# Magneto.net
KiCad netlist of a schematic drawn in Altium Designer
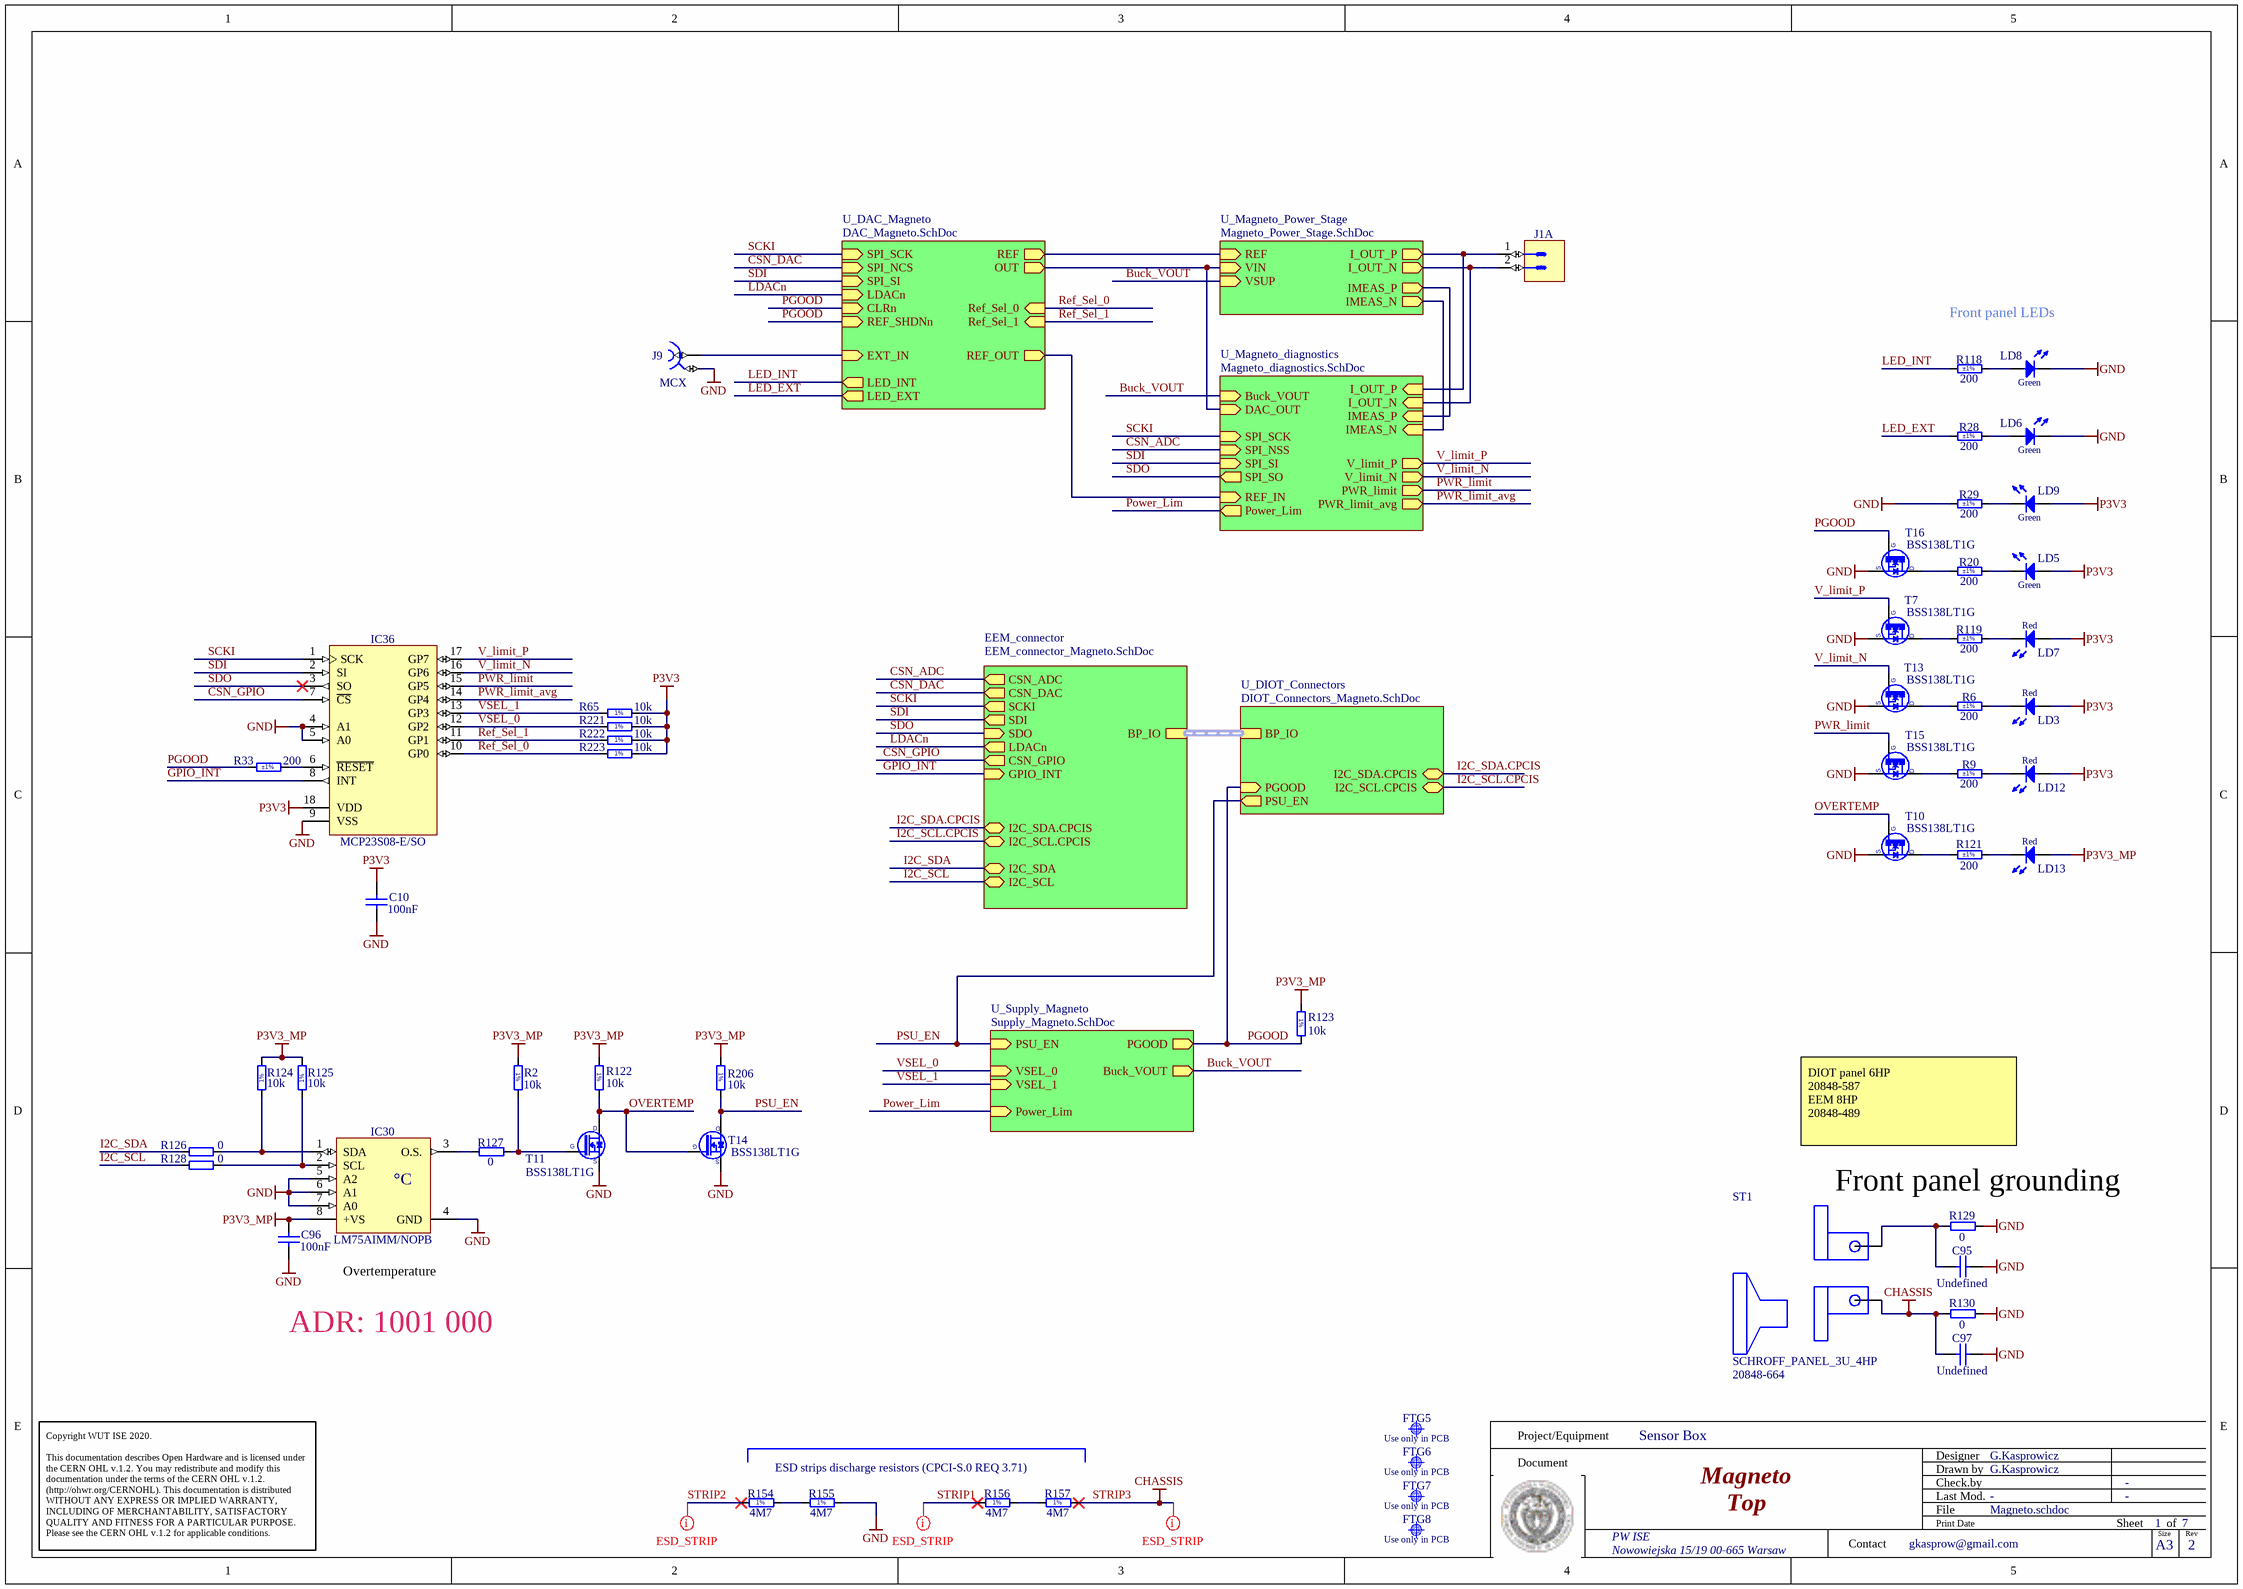
[diagram p0: Magneto.schdoc]

(export (version "E")
  (design (tool "Eeschema 10.0.6"))
  (components
    (comp (ref "C10")
      (value "100nF")
      (footprint "CAPC1005X55N")
      (description "Non-polarised capacitor")
      (fields
        (field (name "PART NUMBER") "CC0402_100NF_16V_10%_X5R")
        (field (name "VOLTAGE") "16V")
        (field (name "AUTHOR") "CERN DEM JLC")
      )
      (libsource (lib "Capacitors") (part "Capacitor - non polarized"))
    )
    (comp (ref "C95")
      (value "Undefined")
      (footprint "CAPC2012X135N")
      (description "Non-polarised capacitor")
      (fields (field (name "PART NUMBER") "CC0805_NO-VALUE") (field (name "AUTHOR") "CERN DEM JLC"))
      (libsource (lib "Capacitors") (part "Capacitor - non polarized"))
    )
    (comp (ref "C96")
      (value "100nF")
      (footprint "CAPC1005X55N")
      (description "Non-polarised capacitor")
      (fields
        (field (name "PART NUMBER") "CC0402_100NF_16V_10%_X5R")
        (field (name "VOLTAGE") "16V")
        (field (name "AUTHOR") "CERN DEM JLC")
      )
      (libsource (lib "Capacitors") (part "Capacitor - non polarized"))
    )
    (comp (ref "C97")
      (value "Undefined")
      (footprint "CAPC2012X135N")
      (description "Non-polarised capacitor")
      (fields (field (name "PART NUMBER") "CC0805_NO-VALUE") (field (name "AUTHOR") "CERN DEM JLC"))
      (libsource (lib "Capacitors") (part "Capacitor - non polarized"))
    )
    (comp (ref "FTG5")
      (value "Use only in PCB")
      (footprint "FIDUCIAL_TOP_C100-200")
      (description "Fiducial Target")
      (fields (field (name "PART NUMBER") "FIDUCIAL_TARGET_C100-200") (field (name "AUTHOR") "CERN DEM JLC"))
      (libsource (lib "Eletro-mechanical") (part "Fiducial Target"))
    )
    (comp (ref "FTG6")
      (value "Use only in PCB")
      (footprint "FIDUCIAL_TOP_S100-200")
      (description "Fiducial Target")
      (fields (field (name "PART NUMBER") "FIDUCIAL_TARGET_S100-200") (field (name "AUTHOR") "CERN DEM JLC"))
      (libsource (lib "Eletro-mechanical") (part "Fiducial Target"))
    )
    (comp (ref "FTG7")
      (value "Use only in PCB")
      (footprint "FIDUCIAL_TOP_S100-200")
      (description "Fiducial Target")
      (fields (field (name "PART NUMBER") "FIDUCIAL_TARGET_S100-200") (field (name "AUTHOR") "CERN DEM JLC"))
      (libsource (lib "Eletro-mechanical") (part "Fiducial Target"))
    )
    (comp (ref "FTG8")
      (value "Use only in PCB")
      (footprint "FIDUCIAL_TOP_S100-200")
      (description "Fiducial Target")
      (fields (field (name "PART NUMBER") "FIDUCIAL_TARGET_S100-200") (field (name "AUTHOR") "CERN DEM JLC"))
      (libsource (lib "Eletro-mechanical") (part "Fiducial Target"))
    )
    (comp (ref "IC30")
      (value "LM75AIMM/NOPB")
      (footprint "SOP65P490X109-8N")
      (description "Digital Temperature Sensor and Thermal Watchdog with Two-Wire Interface")
      (fields (field (name "AUTHOR") "CERN DEM JLC"))
      (libsource (lib "ICs And Semiconductors") (part "LM75"))
    )
    (comp (ref "IC36")
      (value "MCP23S08-E/SO")
      (footprint "SOIC127P1030X265-18N")
      (description "8-Bit I/O Expander with Serial Interface SPI")
      (fields (field (name "AUTHOR") "CERN DEM HF"))
      (libsource (lib "ICs And Semiconductors") (part "MCP23S08-E/SO"))
    )
    (comp (ref "J1")
      (value "~")
      (footprint "PHOENIX_1817615")
      (description "Connector 2 Male+2MTG")
      (fields
        (field (name "PART NUMBER") "1817615 (MC 1,5/ 2-GF-3,5-LR)")
        (field (name "MANUFACTURER1 PART NUMBER") "1817615")
        (field (name "AUTHOR") "CERN DEM BC")
      )
      (libsource (lib "Connectors") (part "Connector 2 Male+2MTG"))
    )
    (comp (ref "J9")
      (value "MCX")
      (footprint "AMPHENOL_919-383J-51A")
      (fields
        (field (name "PART NUMBER") "AMPHENOL_919-383J-51A")
        (field (name "MANUFACTURER1 PART NUMBER") "919-383J-51A")
        (field (name "AUTHOR") "CERN DEM BC")
      )
      (libsource (lib "Connectors") (part "Coax_1Female_1Shield"))
    )
    (comp (ref "LD3")
      (value "Red")
      (footprint "LED_DIALIGHT_555-200")
      (description "LED Red 1C 2A")
      (fields
        (field (name "PART NUMBER") "LED_DIALIGHT_555-2001F")
        (field (name "MANUFACTURER1 PART NUMBER") "555-2001F")
        (field (name "AUTHOR") "CERN DEM JMW")
      )
      (libsource (lib "ICs And Semiconductors") (part "LED Red 1C 2A"))
    )
    (comp (ref "LD5")
      (value "Green")
      (footprint "LED_DIALIGHT_555-230")
      (description "LED Green 1C 2A")
      (fields
        (field (name "PART NUMBER") "LED_DIALIGHT_555-2301F")
        (field (name "MANUFACTURER1 PART NUMBER") "555-2301F")
        (field (name "AUTHOR") "CERN DEM JMW")
      )
      (libsource (lib "ICs And Semiconductors") (part "LED Green 1C 2A"))
    )
    (comp (ref "LD6")
      (value "Green")
      (footprint "LED_DIALIGHT_555-230")
      (description "LED Green 1C 2A")
      (fields
        (field (name "PART NUMBER") "LED_DIALIGHT_555-2301F")
        (field (name "MANUFACTURER1 PART NUMBER") "555-2301F")
        (field (name "AUTHOR") "CERN DEM JMW")
      )
      (libsource (lib "ICs And Semiconductors") (part "LED Green 1C 2A"))
    )
    (comp (ref "LD7")
      (value "Red")
      (footprint "LED_DIALIGHT_555-200")
      (description "LED Red 1C 2A")
      (fields
        (field (name "PART NUMBER") "LED_DIALIGHT_555-2001F")
        (field (name "MANUFACTURER1 PART NUMBER") "555-2001F")
        (field (name "AUTHOR") "CERN DEM JMW")
      )
      (libsource (lib "ICs And Semiconductors") (part "LED Red 1C 2A"))
    )
    (comp (ref "LD8")
      (value "Green")
      (footprint "LED_DIALIGHT_555-230")
      (description "LED Green 1C 2A")
      (fields
        (field (name "PART NUMBER") "LED_DIALIGHT_555-2301F")
        (field (name "MANUFACTURER1 PART NUMBER") "555-2301F")
        (field (name "AUTHOR") "CERN DEM JMW")
      )
      (libsource (lib "ICs And Semiconductors") (part "LED Green 1C 2A"))
    )
    (comp (ref "LD9")
      (value "Green")
      (footprint "LED_DIALIGHT_555-230")
      (description "LED Green 1C 2A")
      (fields
        (field (name "PART NUMBER") "LED_DIALIGHT_555-2301F")
        (field (name "MANUFACTURER1 PART NUMBER") "555-2301F")
        (field (name "AUTHOR") "CERN DEM JMW")
      )
      (libsource (lib "ICs And Semiconductors") (part "LED Green 1C 2A"))
    )
    (comp (ref "LD12")
      (value "Red")
      (footprint "LED_DIALIGHT_555-200")
      (description "LED Red 1C 2A")
      (fields
        (field (name "PART NUMBER") "LED_DIALIGHT_555-2001F")
        (field (name "MANUFACTURER1 PART NUMBER") "555-2001F")
        (field (name "AUTHOR") "CERN DEM JMW")
      )
      (libsource (lib "ICs And Semiconductors") (part "LED Red 1C 2A"))
    )
    (comp (ref "LD13")
      (value "Red")
      (footprint "LED_DIALIGHT_555-200")
      (description "LED Red 1C 2A")
      (fields
        (field (name "PART NUMBER") "LED_DIALIGHT_555-2001F")
        (field (name "MANUFACTURER1 PART NUMBER") "555-2001F")
        (field (name "AUTHOR") "CERN DEM JMW")
      )
      (libsource (lib "ICs And Semiconductors") (part "LED Red 1C 2A"))
    )
    (comp (ref "R2")
      (value "10k")
      (footprint "RESC1005X40N")
      (description "Resistor - 1%")
      (fields
        (field (name "PART NUMBER") "R0402_10K_1%_0.0625W_100PPM")
        (field (name "POWER") "0.0625W")
        (field (name "AUTHOR") "CERN DEM JLC")
      )
      (libsource (lib "Resistors") (part "Resistor - 1%"))
    )
    (comp (ref "R6")
      (value "200")
      (footprint "RESC1608X55N")
      (description "Resistor - 1%")
      (fields
        (field (name "TOLERANCE") "±1%")
        (field (name "PART NUMBER") "R0603_200R_1%_0.1W_100PPM")
        (field (name "POWER") "0.1W")
        (field (name "AUTHOR") "CERN DEM JLC")
      )
      (libsource (lib "") (part "Resistor - 1%_1"))
    )
    (comp (ref "R9")
      (value "200")
      (footprint "RESC1608X55N")
      (description "Resistor - 1%")
      (fields
        (field (name "TOLERANCE") "±1%")
        (field (name "PART NUMBER") "R0603_200R_1%_0.1W_100PPM")
        (field (name "POWER") "0.1W")
        (field (name "AUTHOR") "CERN DEM JLC")
      )
      (libsource (lib "") (part "Resistor - 1%_1"))
    )
    (comp (ref "R20")
      (value "200")
      (footprint "RESC1608X55N")
      (description "Resistor - 1%")
      (fields
        (field (name "TOLERANCE") "±1%")
        (field (name "PART NUMBER") "R0603_200R_1%_0.1W_100PPM")
        (field (name "POWER") "0.1W")
        (field (name "AUTHOR") "CERN DEM JLC")
      )
      (libsource (lib "") (part "Resistor - 1%_1"))
    )
    (comp (ref "R28")
      (value "200")
      (footprint "RESC1608X55N")
      (description "Resistor - 1%")
      (fields
        (field (name "TOLERANCE") "±1%")
        (field (name "PART NUMBER") "R0603_200R_1%_0.1W_100PPM")
        (field (name "POWER") "0.1W")
        (field (name "AUTHOR") "CERN DEM JLC")
      )
      (libsource (lib "") (part "Resistor - 1%_1"))
    )
    (comp (ref "R29")
      (value "200")
      (footprint "RESC1608X55N")
      (description "Resistor - 1%")
      (fields
        (field (name "TOLERANCE") "±1%")
        (field (name "PART NUMBER") "R0603_200R_1%_0.1W_100PPM")
        (field (name "POWER") "0.1W")
        (field (name "AUTHOR") "CERN DEM JLC")
      )
      (libsource (lib "") (part "Resistor - 1%_1"))
    )
    (comp (ref "R33")
      (value "200")
      (footprint "RESC1608X55N")
      (description "Resistor - 1%")
      (fields
        (field (name "TOLERANCE") "±1%")
        (field (name "PART NUMBER") "R0603_200R_1%_0.1W_100PPM")
        (field (name "POWER") "0.1W")
        (field (name "AUTHOR") "CERN DEM JLC")
      )
      (libsource (lib "") (part "Resistor - 1%_1"))
    )
    (comp (ref "R65")
      (value "10k")
      (footprint "RESC1005X40N")
      (description "Resistor - 1%")
      (fields
        (field (name "PART NUMBER") "R0402_10K_1%_0.0625W_100PPM")
        (field (name "POWER") "0.0625W")
        (field (name "AUTHOR") "CERN DEM JLC")
      )
      (libsource (lib "Resistors") (part "Resistor - 1%"))
    )
    (comp (ref "R118")
      (value "200")
      (footprint "RESC1608X55N")
      (description "Resistor - 1%")
      (fields
        (field (name "TOLERANCE") "±1%")
        (field (name "PART NUMBER") "R0603_200R_1%_0.1W_100PPM")
        (field (name "POWER") "0.1W")
        (field (name "AUTHOR") "CERN DEM JLC")
      )
      (libsource (lib "") (part "Resistor - 1%_1"))
    )
    (comp (ref "R119")
      (value "200")
      (footprint "RESC1608X55N")
      (description "Resistor - 1%")
      (fields
        (field (name "TOLERANCE") "±1%")
        (field (name "PART NUMBER") "R0603_200R_1%_0.1W_100PPM")
        (field (name "POWER") "0.1W")
        (field (name "AUTHOR") "CERN DEM JLC")
      )
      (libsource (lib "") (part "Resistor - 1%_1"))
    )
    (comp (ref "R121")
      (value "200")
      (footprint "RESC1608X55N")
      (description "Resistor - 1%")
      (fields
        (field (name "TOLERANCE") "±1%")
        (field (name "PART NUMBER") "R0603_200R_1%_0.1W_100PPM")
        (field (name "POWER") "0.1W")
        (field (name "AUTHOR") "CERN DEM JLC")
      )
      (libsource (lib "") (part "Resistor - 1%_1"))
    )
    (comp (ref "R122")
      (value "10k")
      (footprint "RESC1005X40N")
      (description "Resistor - 1%")
      (fields
        (field (name "PART NUMBER") "R0402_10K_1%_0.0625W_100PPM")
        (field (name "POWER") "0.0625W")
        (field (name "AUTHOR") "CERN DEM JLC")
      )
      (libsource (lib "Resistors") (part "Resistor - 1%"))
    )
    (comp (ref "R123")
      (value "10k")
      (footprint "RESC1005X40N")
      (description "Resistor - 1%")
      (fields
        (field (name "PART NUMBER") "R0402_10K_1%_0.0625W_100PPM")
        (field (name "POWER") "0.0625W")
        (field (name "AUTHOR") "CERN DEM JLC")
      )
      (libsource (lib "Resistors") (part "Resistor - 1%"))
    )
    (comp (ref "R124")
      (value "10k")
      (footprint "RESC1005X40N")
      (description "Resistor - 1%")
      (fields
        (field (name "PART NUMBER") "R0402_10K_1%_0.0625W_100PPM")
        (field (name "POWER") "0.0625W")
        (field (name "AUTHOR") "CERN DEM JLC")
      )
      (libsource (lib "Resistors") (part "Resistor - 1%"))
    )
    (comp (ref "R125")
      (value "10k")
      (footprint "RESC1005X40N")
      (description "Resistor - 1%")
      (fields
        (field (name "PART NUMBER") "R0402_10K_1%_0.0625W_100PPM")
        (field (name "POWER") "0.0625W")
        (field (name "AUTHOR") "CERN DEM JLC")
      )
      (libsource (lib "Resistors") (part "Resistor - 1%"))
    )
    (comp (ref "R126")
      (value "0")
      (footprint "RESC1005X40N")
      (description "Resistor")
      (fields
        (field (name "PART NUMBER") "R0402_0R_JUMPER")
        (field (name "MANUFACTURER") "GENERIC")
        (field (name "AUTHOR") "CERN DEM JLC")
      )
      (libsource (lib "Resistors") (part "Resistor"))
    )
    (comp (ref "R127")
      (value "0")
      (footprint "RESC1005X40N")
      (description "Resistor")
      (fields
        (field (name "PART NUMBER") "R0402_0R_JUMPER")
        (field (name "MANUFACTURER") "GENERIC")
        (field (name "AUTHOR") "CERN DEM JLC")
      )
      (libsource (lib "Resistors") (part "Resistor"))
    )
    (comp (ref "R128")
      (value "0")
      (footprint "RESC1005X40N")
      (description "Resistor")
      (fields
        (field (name "PART NUMBER") "R0402_0R_JUMPER")
        (field (name "MANUFACTURER") "GENERIC")
        (field (name "AUTHOR") "CERN DEM JLC")
      )
      (libsource (lib "Resistors") (part "Resistor"))
    )
    (comp (ref "R129")
      (value "0")
      (footprint "RESC2012X60N")
      (description "Resistor")
      (fields
        (field (name "PART NUMBER") "R0805_0R_JUMPER")
        (field (name "MANUFACTURER") "GENERIC")
        (field (name "AUTHOR") "CERN DEM JLC")
      )
      (libsource (lib "Resistors") (part "Resistor"))
    )
    (comp (ref "R130")
      (value "0")
      (footprint "RESC2012X60N")
      (description "Resistor")
      (fields
        (field (name "PART NUMBER") "R0805_0R_JUMPER")
        (field (name "MANUFACTURER") "GENERIC")
        (field (name "AUTHOR") "CERN DEM JLC")
      )
      (libsource (lib "Resistors") (part "Resistor"))
    )
    (comp (ref "R154")
      (value "4M7")
      (footprint "RESC2113X55N")
      (description "Resistor - 1%")
      (fields
        (field (name "PART NUMBER") "R0805_4M7_1%_0.125W_100PPM_VISHAY_CRCW e3")
        (field (name "POWER") "0.125W")
        (field (name "AUTHOR") "CERN DEM BR")
      )
      (libsource (lib "Resistors") (part "Resistor - 1%"))
    )
    (comp (ref "R155")
      (value "4M7")
      (footprint "RESC2113X55N")
      (description "Resistor - 1%")
      (fields
        (field (name "PART NUMBER") "R0805_4M7_1%_0.125W_100PPM_VISHAY_CRCW e3")
        (field (name "POWER") "0.125W")
        (field (name "AUTHOR") "CERN DEM BR")
      )
      (libsource (lib "Resistors") (part "Resistor - 1%"))
    )
    (comp (ref "R156")
      (value "4M7")
      (footprint "RESC2113X55N")
      (description "Resistor - 1%")
      (fields
        (field (name "PART NUMBER") "R0805_4M7_1%_0.125W_100PPM_VISHAY_CRCW e3")
        (field (name "POWER") "0.125W")
        (field (name "AUTHOR") "CERN DEM BR")
      )
      (libsource (lib "Resistors") (part "Resistor - 1%"))
    )
    (comp (ref "R157")
      (value "4M7")
      (footprint "RESC2113X55N")
      (description "Resistor - 1%")
      (fields
        (field (name "PART NUMBER") "R0805_4M7_1%_0.125W_100PPM_VISHAY_CRCW e3")
        (field (name "POWER") "0.125W")
        (field (name "AUTHOR") "CERN DEM BR")
      )
      (libsource (lib "Resistors") (part "Resistor - 1%"))
    )
    (comp (ref "R206")
      (value "10k")
      (footprint "RESC1005X40N")
      (description "Resistor - 1%")
      (fields
        (field (name "PART NUMBER") "R0402_10K_1%_0.0625W_100PPM")
        (field (name "POWER") "0.0625W")
        (field (name "AUTHOR") "CERN DEM JLC")
      )
      (libsource (lib "Resistors") (part "Resistor - 1%"))
    )
    (comp (ref "R221")
      (value "10k")
      (footprint "RESC1005X40N")
      (description "Resistor - 1%")
      (fields
        (field (name "PART NUMBER") "R0402_10K_1%_0.0625W_100PPM")
        (field (name "POWER") "0.0625W")
        (field (name "AUTHOR") "CERN DEM JLC")
      )
      (libsource (lib "Resistors") (part "Resistor - 1%"))
    )
    (comp (ref "R222")
      (value "10k")
      (footprint "RESC1005X40N")
      (description "Resistor - 1%")
      (fields
        (field (name "PART NUMBER") "R0402_10K_1%_0.0625W_100PPM")
        (field (name "POWER") "0.0625W")
        (field (name "AUTHOR") "CERN DEM JLC")
      )
      (libsource (lib "Resistors") (part "Resistor - 1%"))
    )
    (comp (ref "R223")
      (value "10k")
      (footprint "RESC1005X40N")
      (description "Resistor - 1%")
      (fields
        (field (name "PART NUMBER") "R0402_10K_1%_0.0625W_100PPM")
        (field (name "POWER") "0.0625W")
        (field (name "AUTHOR") "CERN DEM JLC")
      )
      (libsource (lib "Resistors") (part "Resistor - 1%"))
    )
    (comp (ref "ST1")
      (value "SCHROFF_PANEL_3U_4HP")
      (footprint "SCHROFF_PANEL_3HP_4U")
      (description "Schroff 3HP 4U EUROCARD Panel Kit")
      (fields
        (field (name "MANUFACTURER1 PART NUMBER") "20818-017")
        (field (name "MANUFACTURER PART NUMBER 2") "20848-664")
      )
      (libsource (lib "Mechanical") (part "SCHROFF_PANEL_3U_4HP"))
    )
    (comp (ref "T7")
      (value "BSS138LT1G")
      (footprint "SOT95P240X110-3N")
      (description "N-CHANNEL MOSFET WITH DIODE")
      (fields (field (name "AUTHOR") "CERN DEM JLC"))
      (libsource (lib "ICs And Semiconductors") (part "N-MOSFET-D 1G 2S 3D"))
    )
    (comp (ref "T10")
      (value "BSS138LT1G")
      (footprint "SOT95P240X110-3N")
      (description "N-CHANNEL MOSFET WITH DIODE")
      (fields (field (name "AUTHOR") "CERN DEM JLC"))
      (libsource (lib "ICs And Semiconductors") (part "N-MOSFET-D 1G 2S 3D"))
    )
    (comp (ref "T11")
      (value "BSS138LT1G")
      (footprint "SOT95P240X110-3N")
      (description "N-CHANNEL MOSFET WITH DIODE")
      (fields (field (name "AUTHOR") "CERN DEM JLC"))
      (libsource (lib "") (part "N-MOSFET-D 1G 2S 3D_1"))
    )
    (comp (ref "T13")
      (value "BSS138LT1G")
      (footprint "SOT95P240X110-3N")
      (description "N-CHANNEL MOSFET WITH DIODE")
      (fields (field (name "AUTHOR") "CERN DEM JLC"))
      (libsource (lib "ICs And Semiconductors") (part "N-MOSFET-D 1G 2S 3D"))
    )
    (comp (ref "T14")
      (value "BSS138LT1G")
      (footprint "SOT95P240X110-3N")
      (description "N-CHANNEL MOSFET WITH DIODE")
      (fields (field (name "AUTHOR") "CERN DEM JLC"))
      (libsource (lib "") (part "N-MOSFET-D 1G 2S 3D_1"))
    )
    (comp (ref "T15")
      (value "BSS138LT1G")
      (footprint "SOT95P240X110-3N")
      (description "N-CHANNEL MOSFET WITH DIODE")
      (fields (field (name "AUTHOR") "CERN DEM JLC"))
      (libsource (lib "ICs And Semiconductors") (part "N-MOSFET-D 1G 2S 3D"))
    )
    (comp (ref "T16")
      (value "BSS138LT1G")
      (footprint "SOT95P240X110-3N")
      (description "N-CHANNEL MOSFET WITH DIODE")
      (fields (field (name "AUTHOR") "CERN DEM JLC"))
      (libsource (lib "ICs And Semiconductors") (part "N-MOSFET-D 1G 2S 3D"))
    )
  )
  (nets
    (net (code "5") (name "/CSN_GPIO") (class "Default")
      (node (ref "IC36") (pin "7") (pinfunction "~{CS}_7") (pintype "input"))
    )
    (net (code "6") (name "/EXT_IN") (class "Default")
      (node (ref "J9") (pin "1") (pinfunction "1_1") (pintype "bidirectional"))
    )
    (net (code "7") (name "/GPIO_INT") (class "Default")
      (node (ref "IC36") (pin "8") (pinfunction "INT_8") (pintype "output"))
    )
    (net (code "8") (name "/I2C_SCL") (class "Default")
      (node (ref "R128") (pin "1") (pinfunction "1_1") (pintype "passive"))
    )
    (net (code "10") (name "/I2C_SDA") (class "Default")
      (node (ref "R126") (pin "1") (pinfunction "1_1") (pintype "passive"))
    )
    (net (code "14") (name "/I_OUT_N") (class "Default")
      (node (ref "J1") (pin "2") (pinfunction "2_2") (pintype "bidirectional"))
    )
    (net (code "15") (name "/I_OUT_P") (class "Default")
      (node (ref "J1") (pin "1") (pinfunction "1_1") (pintype "bidirectional"))
    )
    (net (code "17") (name "/LED_EXT") (class "Default")
      (node (ref "R28") (pin "1") (pinfunction "1_1") (pintype "passive"))
    )
    (net (code "18") (name "/LED_INT") (class "Default")
      (node (ref "R118") (pin "1") (pinfunction "1_1") (pintype "passive"))
    )
    (net (code "20") (name "/OVERTEMP") (class "Default")
      (node (ref "R122") (pin "2") (pinfunction "2_2") (pintype "passive"))
      (node (ref "T10") (pin "1") (pinfunction "G_1") (pintype "passive"))
      (node (ref "T11") (pin "3") (pinfunction "D_3") (pintype "passive"))
      (node (ref "T14") (pin "1") (pinfunction "G_1") (pintype "passive"))
    )
    (net (code "21") (name "/PGOOD") (class "Default")
      (node (ref "R123") (pin "2") (pinfunction "2_2") (pintype "passive"))
      (node (ref "R33") (pin "1") (pinfunction "1_1") (pintype "passive"))
      (node (ref "T16") (pin "1") (pinfunction "G_1") (pintype "passive"))
    )
    (net (code "22") (name "/PSU_EN") (class "Default")
      (node (ref "R206") (pin "2") (pinfunction "2_2") (pintype "passive"))
      (node (ref "T14") (pin "3") (pinfunction "D_3") (pintype "passive"))
    )
    (net (code "23") (name "/PWR_limit") (class "Default")
      (node (ref "IC36") (pin "15") (pinfunction "GP5_15") (pintype "bidirectional"))
      (node (ref "T15") (pin "1") (pinfunction "G_1") (pintype "passive"))
    )
    (net (code "24") (name "/PWR_limit_avg") (class "Default")
      (node (ref "IC36") (pin "14") (pinfunction "GP4_14") (pintype "bidirectional"))
    )
    (net (code "28") (name "/Ref_Sel_0") (class "Default")
      (node (ref "IC36") (pin "10") (pinfunction "GP0_10") (pintype "bidirectional"))
      (node (ref "R223") (pin "1") (pinfunction "1_1") (pintype "passive"))
    )
    (net (code "29") (name "/Ref_Sel_1") (class "Default")
      (node (ref "IC36") (pin "11") (pinfunction "GP1_11") (pintype "bidirectional"))
      (node (ref "R222") (pin "1") (pinfunction "1_1") (pintype "passive"))
    )
    (net (code "30") (name "/SCKI") (class "Default")
      (node (ref "IC36") (pin "1") (pinfunction "SCK_1") (pintype "input"))
    )
    (net (code "31") (name "/SDI") (class "Default")
      (node (ref "IC36") (pin "2") (pinfunction "SI_2") (pintype "input"))
    )
    (net (code "32") (name "/SDO") (class "Default")
      (node (ref "IC36") (pin "3") (pinfunction "SO_3") (pintype "output+no_connect"))
    )
    (net (code "33") (name "/STRIP1") (class "Default")
      (node (ref "R156") (pin "1") (pinfunction "1_1") (pintype "passive+no_connect"))
    )
    (net (code "34") (name "/STRIP2") (class "Default")
      (node (ref "R154") (pin "1") (pinfunction "1_1") (pintype "passive+no_connect"))
    )
    (net (code "35") (name "/VSEL_0") (class "Default")
      (node (ref "IC36") (pin "12") (pinfunction "GP2_12") (pintype "bidirectional"))
      (node (ref "R221") (pin "1") (pinfunction "1_1") (pintype "passive"))
    )
    (net (code "36") (name "/VSEL_1") (class "Default")
      (node (ref "IC36") (pin "13") (pinfunction "GP3_13") (pintype "bidirectional"))
      (node (ref "R65") (pin "1") (pinfunction "1_1") (pintype "passive"))
    )
    (net (code "37") (name "/V_limit_N") (class "Default")
      (node (ref "IC36") (pin "16") (pinfunction "GP6_16") (pintype "bidirectional"))
      (node (ref "T13") (pin "1") (pinfunction "G_1") (pintype "passive"))
    )
    (net (code "38") (name "/V_limit_P") (class "Default")
      (node (ref "IC36") (pin "17") (pinfunction "GP7_17") (pintype "bidirectional"))
      (node (ref "T7") (pin "1") (pinfunction "G_1") (pintype "passive"))
    )
    (net (code "39") (name "CHASSIS") (class "Default")
      (node (ref "C97") (pin "1") (pinfunction "1_1") (pintype "passive"))
      (node (ref "R130") (pin "1") (pinfunction "1_1") (pintype "passive"))
      (node (ref "R157") (pin "2") (pinfunction "2_2") (pintype "passive"))
      (node (ref "ST1") (pin "0") (pinfunction "0_0") (pintype "passive"))
    )
    (net (code "40") (name "GND") (class "Default")
      (node (ref "C10") (pin "1") (pinfunction "1_1") (pintype "passive"))
      (node (ref "C95") (pin "2") (pinfunction "2_2") (pintype "passive"))
      (node (ref "C96") (pin "1") (pinfunction "1_1") (pintype "passive"))
      (node (ref "C97") (pin "2") (pinfunction "2_2") (pintype "passive"))
      (node (ref "IC30") (pin "4") (pinfunction "GND_4") (pintype "power_in"))
      (node (ref "IC30") (pin "5") (pinfunction "A2_5") (pintype "input"))
      (node (ref "IC30") (pin "6") (pinfunction "A1_6") (pintype "input"))
      (node (ref "IC30") (pin "7") (pinfunction "A0_7") (pintype "input"))
      (node (ref "IC36") (pin "4") (pinfunction "A1_4") (pintype "input"))
      (node (ref "IC36") (pin "5") (pinfunction "A0_5") (pintype "input"))
      (node (ref "IC36") (pin "9") (pinfunction "VSS_9") (pintype "power_in"))
      (node (ref "J9") (pin "2") (pinfunction "2_2") (pintype "bidirectional"))
      (node (ref "LD6") (pin "1") (pinfunction "C_1") (pintype "passive"))
      (node (ref "LD8") (pin "1") (pinfunction "C_1") (pintype "passive"))
      (node (ref "R129") (pin "2") (pinfunction "2_2") (pintype "passive"))
      (node (ref "R130") (pin "2") (pinfunction "2_2") (pintype "passive"))
      (node (ref "R155") (pin "2") (pinfunction "2_2") (pintype "passive"))
      (node (ref "R29") (pin "2") (pinfunction "2_2") (pintype "passive"))
      (node (ref "T10") (pin "2") (pinfunction "S_2") (pintype "passive"))
      (node (ref "T11") (pin "2") (pinfunction "S_2") (pintype "passive"))
      (node (ref "T13") (pin "2") (pinfunction "S_2") (pintype "passive"))
      (node (ref "T14") (pin "2") (pinfunction "S_2") (pintype "passive"))
      (node (ref "T15") (pin "2") (pinfunction "S_2") (pintype "passive"))
      (node (ref "T16") (pin "2") (pinfunction "S_2") (pintype "passive"))
      (node (ref "T7") (pin "2") (pinfunction "S_2") (pintype "passive"))
    )
    (net (code "41") (name "Net-(C95-Pad1)") (class "Default")
      (node (ref "C95") (pin "1") (pinfunction "1_1") (pintype "passive"))
      (node (ref "R129") (pin "1") (pinfunction "1_1") (pintype "passive"))
      (node (ref "ST1") (pin "1") (pinfunction "1_1") (pintype "passive"))
    )
    (net (code "42") (name "Net-(IC30-O.S.)") (class "Default")
      (node (ref "IC30") (pin "3") (pinfunction "O.S._3") (pintype "output"))
      (node (ref "R127") (pin "1") (pinfunction "1_1") (pintype "passive"))
    )
    (net (code "43") (name "Net-(IC30-SCL)") (class "Default")
      (node (ref "IC30") (pin "2") (pinfunction "SCL_2") (pintype "input"))
      (node (ref "R125") (pin "1") (pinfunction "1_1") (pintype "passive"))
      (node (ref "R128") (pin "2") (pinfunction "2_2") (pintype "passive"))
    )
    (net (code "44") (name "Net-(IC30-SDA)") (class "Default")
      (node (ref "IC30") (pin "1") (pinfunction "SDA_1") (pintype "bidirectional"))
      (node (ref "R124") (pin "1") (pinfunction "1_1") (pintype "passive"))
      (node (ref "R126") (pin "2") (pinfunction "2_2") (pintype "passive"))
    )
    (net (code "45") (name "Net-(IC36-~{RESET})") (class "Default")
      (node (ref "IC36") (pin "6") (pinfunction "~{RESET}_6") (pintype "input"))
      (node (ref "R33") (pin "2") (pinfunction "2_2") (pintype "passive"))
    )
    (net (code "46") (name "Net-(LD3-C)") (class "Default")
      (node (ref "LD3") (pin "1") (pinfunction "C_1") (pintype "passive"))
      (node (ref "R6") (pin "2") (pinfunction "2_2") (pintype "passive"))
    )
    (net (code "47") (name "Net-(LD5-C)") (class "Default")
      (node (ref "LD5") (pin "1") (pinfunction "C_1") (pintype "passive"))
      (node (ref "R20") (pin "1") (pinfunction "1_1") (pintype "passive"))
    )
    (net (code "48") (name "Net-(LD6-A)") (class "Default")
      (node (ref "LD6") (pin "2") (pinfunction "A_2") (pintype "passive"))
      (node (ref "R28") (pin "2") (pinfunction "2_2") (pintype "passive"))
    )
    (net (code "49") (name "Net-(LD7-C)") (class "Default")
      (node (ref "LD7") (pin "1") (pinfunction "C_1") (pintype "passive"))
      (node (ref "R119") (pin "2") (pinfunction "2_2") (pintype "passive"))
    )
    (net (code "50") (name "Net-(LD8-A)") (class "Default")
      (node (ref "LD8") (pin "2") (pinfunction "A_2") (pintype "passive"))
      (node (ref "R118") (pin "2") (pinfunction "2_2") (pintype "passive"))
    )
    (net (code "51") (name "Net-(LD9-C)") (class "Default")
      (node (ref "LD9") (pin "1") (pinfunction "C_1") (pintype "passive"))
      (node (ref "R29") (pin "1") (pinfunction "1_1") (pintype "passive"))
    )
    (net (code "52") (name "Net-(LD12-C)") (class "Default")
      (node (ref "LD12") (pin "1") (pinfunction "C_1") (pintype "passive"))
      (node (ref "R9") (pin "2") (pinfunction "2_2") (pintype "passive"))
    )
    (net (code "53") (name "Net-(LD13-C)") (class "Default")
      (node (ref "LD13") (pin "1") (pinfunction "C_1") (pintype "passive"))
      (node (ref "R121") (pin "2") (pinfunction "2_2") (pintype "passive"))
    )
    (net (code "54") (name "Net-(R154-Pad2)") (class "Default")
      (node (ref "R154") (pin "2") (pinfunction "2_2") (pintype "passive"))
      (node (ref "R155") (pin "1") (pinfunction "1_1") (pintype "passive"))
    )
    (net (code "55") (name "Net-(R156-Pad2)") (class "Default")
      (node (ref "R156") (pin "2") (pinfunction "2_2") (pintype "passive"))
      (node (ref "R157") (pin "1") (pinfunction "1_1") (pintype "passive"))
    )
    (net (code "56") (name "Net-(T7-D)") (class "Default")
      (node (ref "R119") (pin "1") (pinfunction "1_1") (pintype "passive"))
      (node (ref "T7") (pin "3") (pinfunction "D_3") (pintype "passive"))
    )
    (net (code "57") (name "Net-(T10-D)") (class "Default")
      (node (ref "R121") (pin "1") (pinfunction "1_1") (pintype "passive"))
      (node (ref "T10") (pin "3") (pinfunction "D_3") (pintype "passive"))
    )
    (net (code "58") (name "Net-(T11-G)") (class "Default")
      (node (ref "R127") (pin "2") (pinfunction "2_2") (pintype "passive"))
      (node (ref "R2") (pin "2") (pinfunction "2_2") (pintype "passive"))
      (node (ref "T11") (pin "1") (pinfunction "G_1") (pintype "passive"))
    )
    (net (code "59") (name "Net-(T13-D)") (class "Default")
      (node (ref "R6") (pin "1") (pinfunction "1_1") (pintype "passive"))
      (node (ref "T13") (pin "3") (pinfunction "D_3") (pintype "passive"))
    )
    (net (code "60") (name "Net-(T15-D)") (class "Default")
      (node (ref "R9") (pin "1") (pinfunction "1_1") (pintype "passive"))
      (node (ref "T15") (pin "3") (pinfunction "D_3") (pintype "passive"))
    )
    (net (code "61") (name "Net-(T16-D)") (class "Default")
      (node (ref "R20") (pin "2") (pinfunction "2_2") (pintype "passive"))
      (node (ref "T16") (pin "3") (pinfunction "D_3") (pintype "passive"))
    )
    (net (code "62") (name "P3V3") (class "Default")
      (node (ref "C10") (pin "2") (pinfunction "2_2") (pintype "passive"))
      (node (ref "IC36") (pin "18") (pinfunction "VDD_18") (pintype "power_in"))
      (node (ref "LD12") (pin "2") (pinfunction "A_2") (pintype "passive"))
      (node (ref "LD3") (pin "2") (pinfunction "A_2") (pintype "passive"))
      (node (ref "LD5") (pin "2") (pinfunction "A_2") (pintype "passive"))
      (node (ref "LD7") (pin "2") (pinfunction "A_2") (pintype "passive"))
      (node (ref "LD9") (pin "2") (pinfunction "A_2") (pintype "passive"))
      (node (ref "R221") (pin "2") (pinfunction "2_2") (pintype "passive"))
      (node (ref "R222") (pin "2") (pinfunction "2_2") (pintype "passive"))
      (node (ref "R223") (pin "2") (pinfunction "2_2") (pintype "passive"))
      (node (ref "R65") (pin "2") (pinfunction "2_2") (pintype "passive"))
    )
    (net (code "63") (name "P3V3_MP") (class "Default")
      (node (ref "C96") (pin "2") (pinfunction "2_2") (pintype "passive"))
      (node (ref "IC30") (pin "8") (pinfunction "+VS_8") (pintype "power_in"))
      (node (ref "LD13") (pin "2") (pinfunction "A_2") (pintype "passive"))
      (node (ref "R122") (pin "1") (pinfunction "1_1") (pintype "passive"))
      (node (ref "R123") (pin "1") (pinfunction "1_1") (pintype "passive"))
      (node (ref "R124") (pin "2") (pinfunction "2_2") (pintype "passive"))
      (node (ref "R125") (pin "2") (pinfunction "2_2") (pintype "passive"))
      (node (ref "R2") (pin "1") (pinfunction "1_1") (pintype "passive"))
      (node (ref "R206") (pin "1") (pinfunction "1_1") (pintype "passive"))
    )
  )
)
